# EEZ_DIB_AUX_PS_r3B3.net
KiCad netlist of a schematic drawn in EAGLE
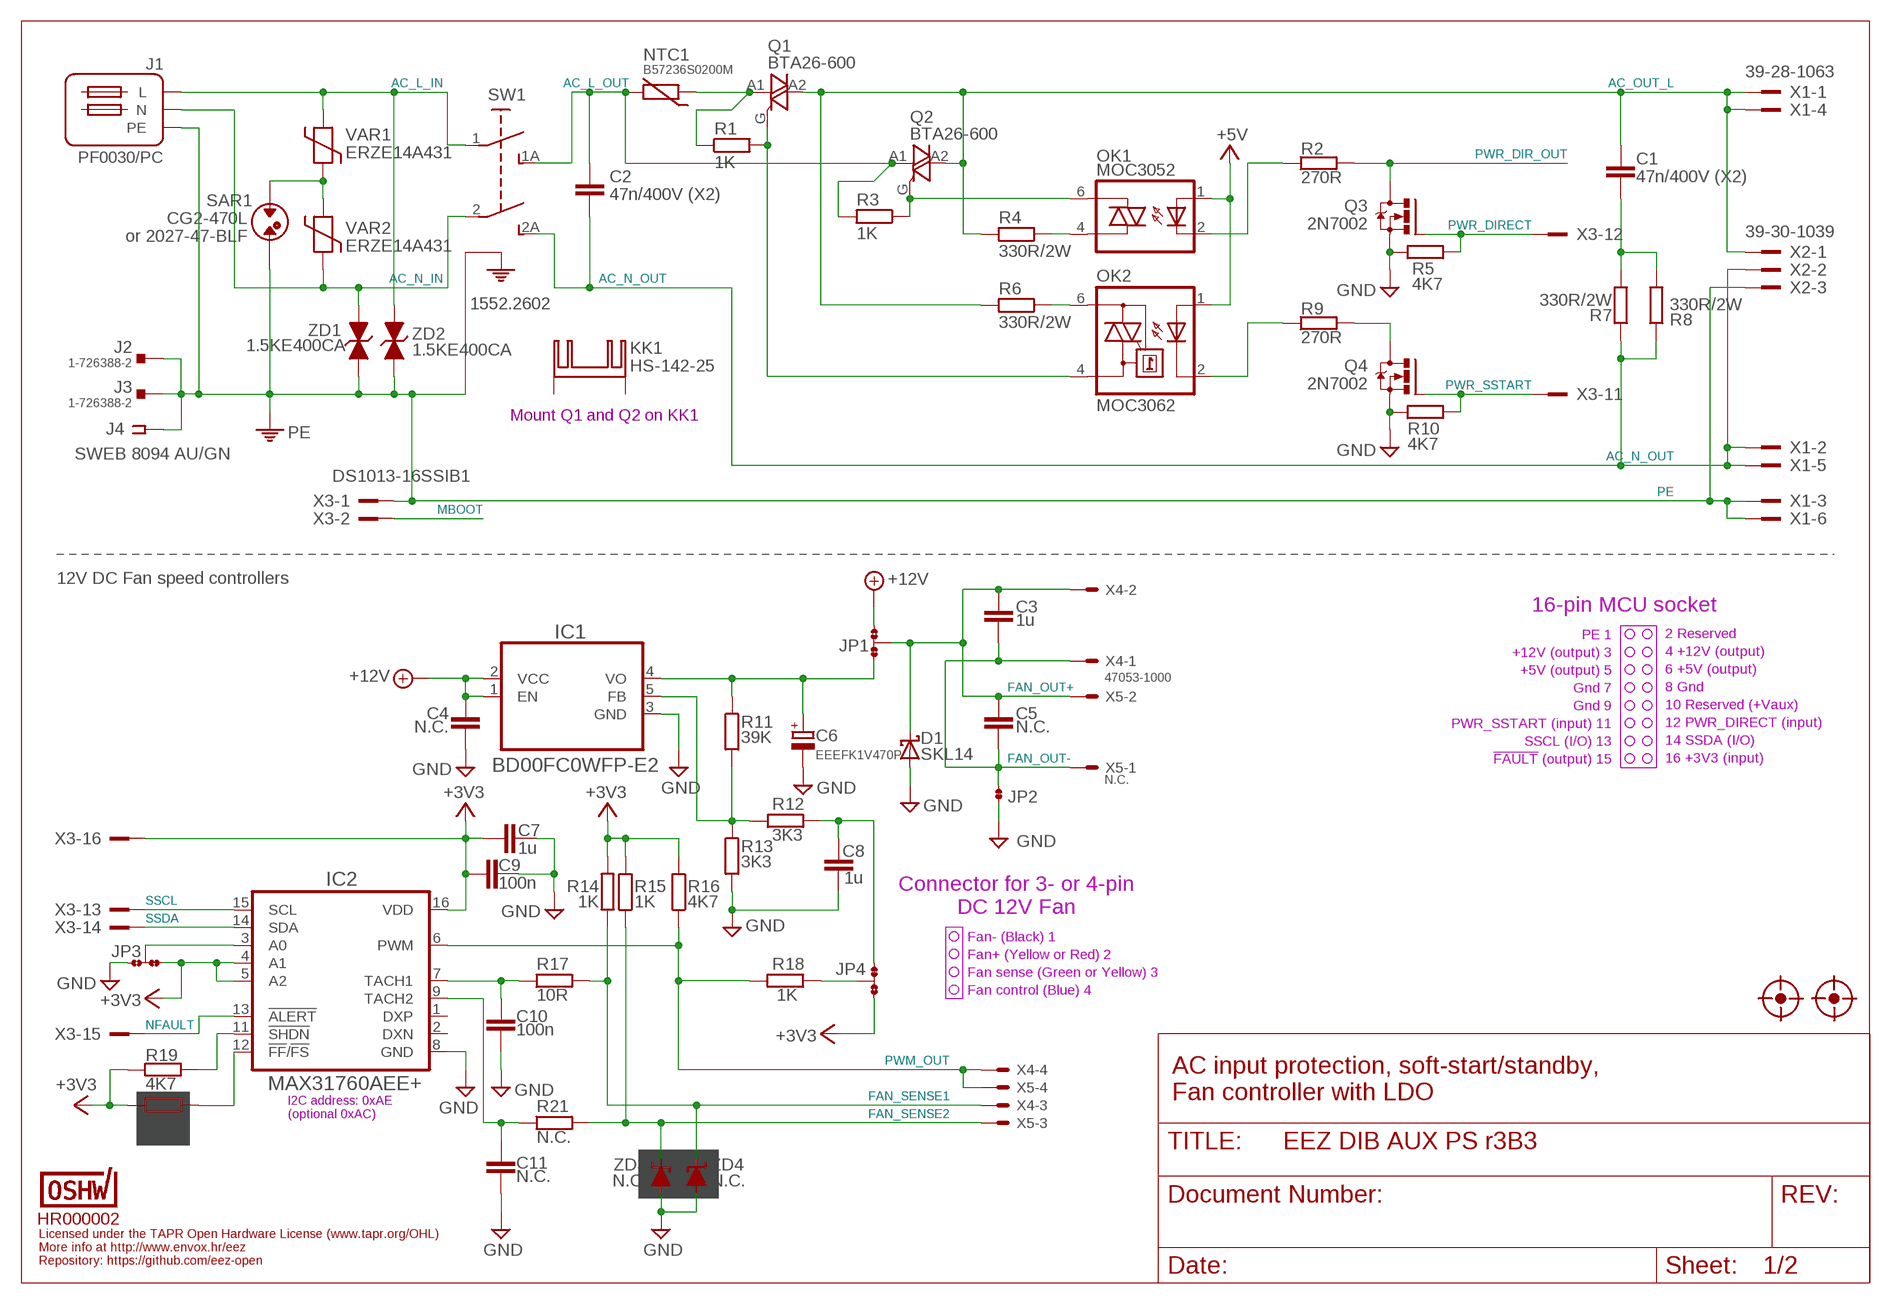
[diagram p0: schematic, sheet 1]
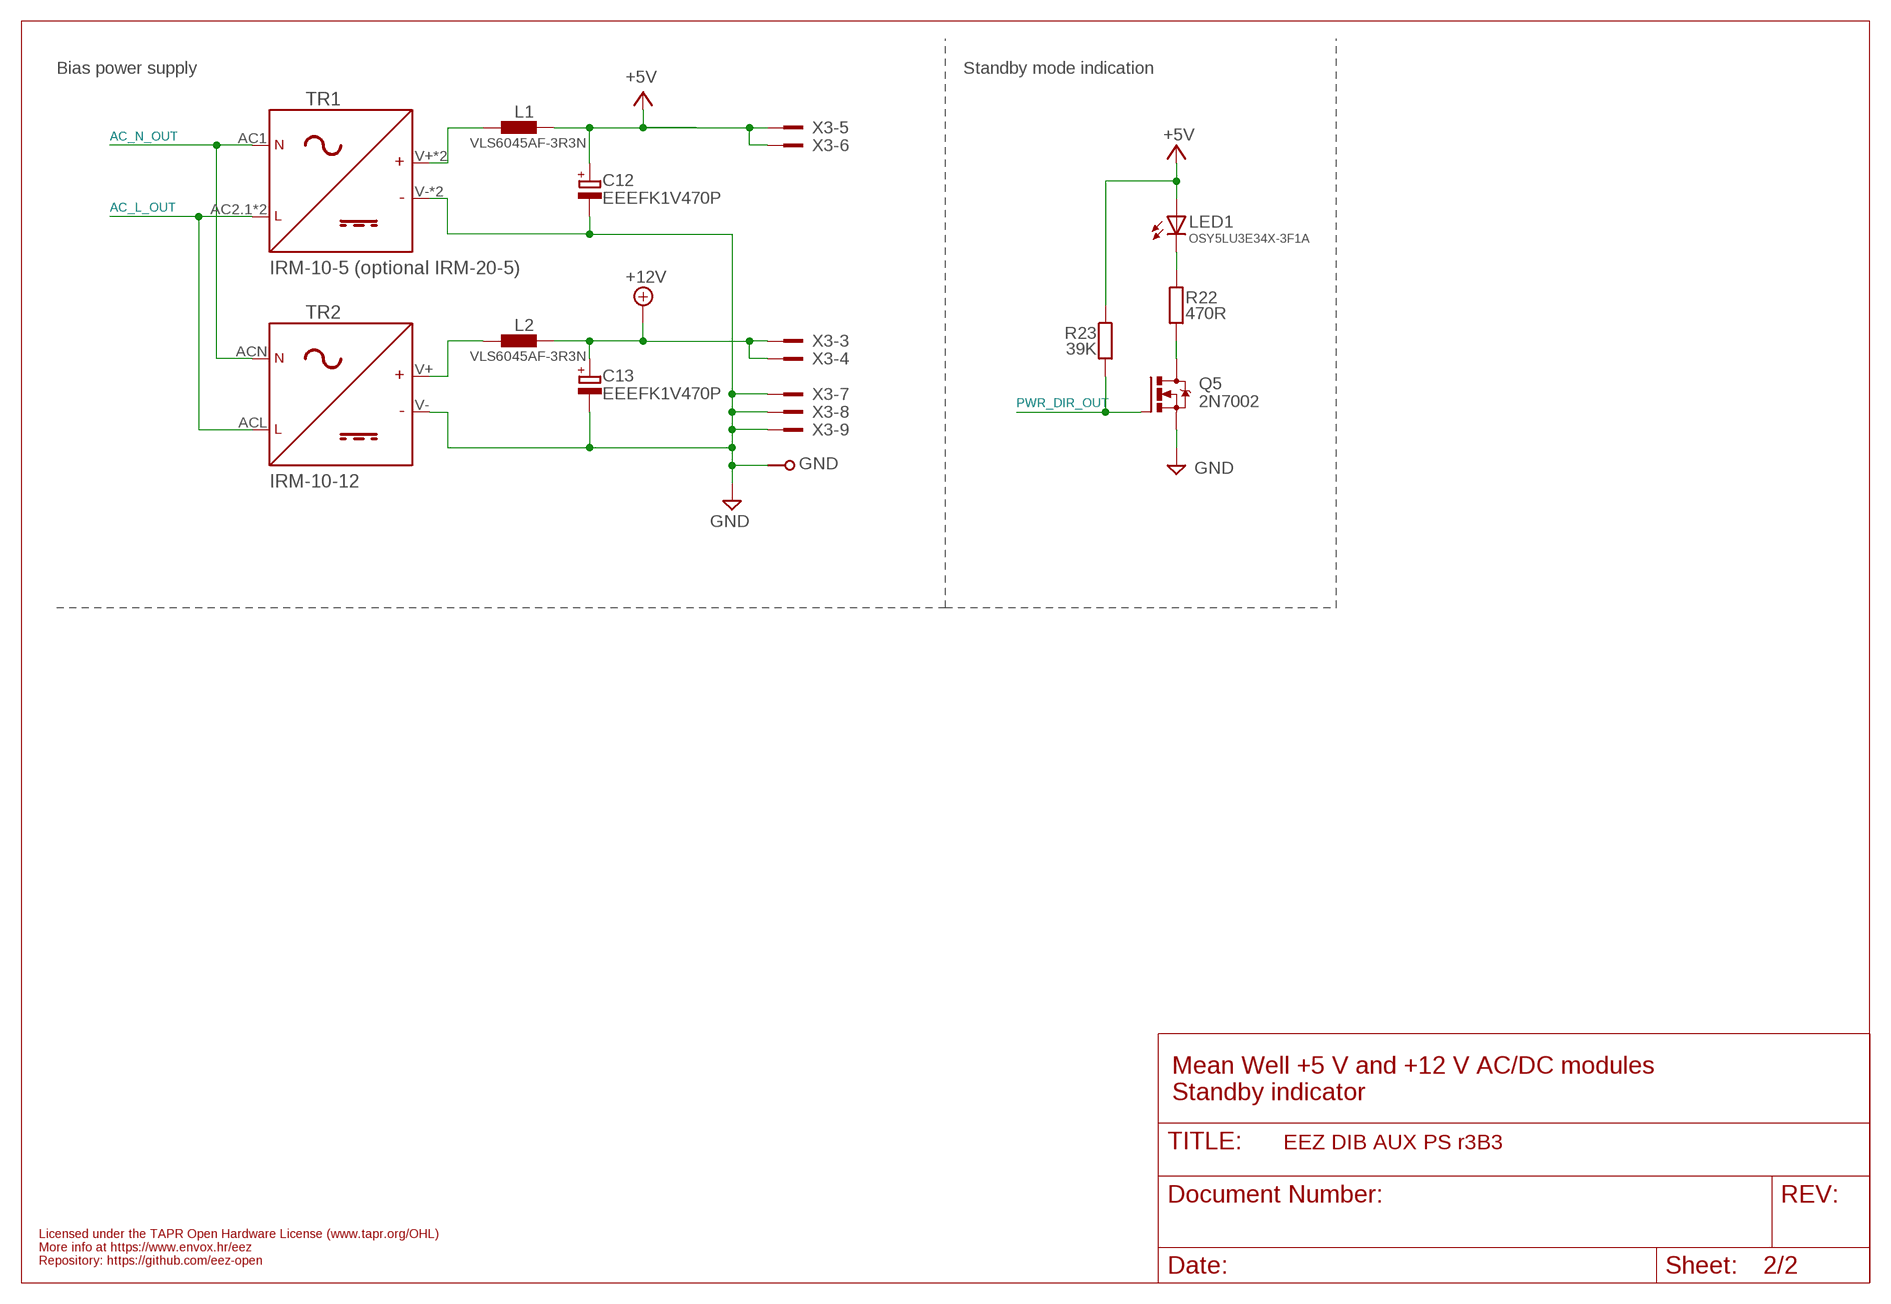
[diagram p1: schematic, sheet 2]

(export (version "E")
  (design (tool "Eeschema 10.0.6"))
  (components
    (comp (ref "C12")
      (value "EEEFK1V470P")
      (footprint "eagle-import:CAPAE660X610N")
      (libsource (lib "eagle-import") (part "ECAPPANASONIC_H"))
    )
    (comp (ref "C13")
      (value "EEEFK1V470P")
      (footprint "eagle-import:CAPAE660X610N")
      (libsource (lib "eagle-import") (part "ECAPPANASONIC_H"))
    )
    (comp (ref "GND")
      (value "PCB_TEST_TABSHIELD")
      (footprint "eagle-import:PCB_SHIELD_TAB")
      (libsource (lib "eagle-import") (part "PCB_TEST_TABSHIELD"))
    )
    (comp (ref "L1")
      (value "VLS6045AF-3R3N")
      (footprint "eagle-import:COILCRAFT_HPI0630")
      (libsource (lib "eagle-import") (part "COILCRAFT_HPI0630"))
    )
    (comp (ref "L2")
      (value "VLS6045AF-3R3N")
      (footprint "eagle-import:COILCRAFT_HPI0630")
      (libsource (lib "eagle-import") (part "COILCRAFT_HPI0630"))
    )
    (comp (ref "LED1")
      (value "OSY5LU3E34X-3F1A")
      (footprint "eagle-import:OSG8")
      (libsource (lib "eagle-import") (part "LEDOSG8"))
    )
    (comp (ref "Q5")
      (value "2N7002")
      (footprint "eagle-import:SOT103P240X110-3N")
      (fields
        (field (name "MPN") "2N7002-7-F")
        (field (name "MPN_1") "2N7002-7-F")
        (field (name "OC_FARNELL") "1713823")
        (field (name "OC_NEWARK") "25R5679")
        (field (name "PACKAGE") "SOT-23-3")
        (field (name "SUPPLIER") "DIODES INC.")
      )
      (libsource (lib "eagle-import") (part "2N7002"))
    )
    (comp (ref "R22")
      (value "470R")
      (footprint "eagle-import:R0805")
      (libsource (lib "eagle-import") (part "R-EU_R0805"))
    )
    (comp (ref "R23")
      (value "39K")
      (footprint "eagle-import:R0805")
      (libsource (lib "eagle-import") (part "R-EU_R0805"))
    )
    (comp (ref "TR1")
      (value "IRM-10-5 (optional IRM-20-5)")
      (footprint "eagle-import:IRM-10_20_COMBO")
      (libsource (lib "eagle-import") (part "AC_DC_ADAPTERIRM10/20"))
    )
    (comp (ref "TR2")
      (value "IRM-10-12")
      (footprint "eagle-import:IRM-10")
      (libsource (lib "eagle-import") (part "AC_DC_ADAPTERIRM10"))
    )
    (comp (ref "X3")
      (value "DS1013-16SSIB1")
      (footprint "eagle-import:IDC-16PIN")
      (libsource (lib "eagle-import") (part "IDC-16PIN"))
    )
    (comp (ref "C1")
      (value "47n/400V (X2)")
      (footprint "eagle-import:C102-054X133")
      (libsource (lib "eagle-import") (part "C-EU102-054X133"))
    )
    (comp (ref "C2")
      (value "47n/400V (X2)")
      (footprint "eagle-import:C102-054X133")
      (libsource (lib "eagle-import") (part "C-EU102-054X133"))
    )
    (comp (ref "C3")
      (value "1u")
      (footprint "eagle-import:C0805")
      (libsource (lib "eagle-import") (part "C-EUC0805"))
    )
    (comp (ref "C4")
      (value "N.C.")
      (footprint "eagle-import:C0805")
      (libsource (lib "eagle-import") (part "C-EUC0805"))
    )
    (comp (ref "C5")
      (value "N.C.")
      (footprint "eagle-import:C0805")
      (libsource (lib "eagle-import") (part "C-EUC0805"))
    )
    (comp (ref "C6")
      (value "EEEFK1V470P")
      (footprint "eagle-import:CAPAE660X610N")
      (libsource (lib "eagle-import") (part "ECAPPANASONIC_H"))
    )
    (comp (ref "C7")
      (value "1u")
      (footprint "eagle-import:C0805")
      (libsource (lib "eagle-import") (part "C-EUC0805"))
    )
    (comp (ref "C8")
      (value "1u")
      (footprint "eagle-import:C0805")
      (libsource (lib "eagle-import") (part "C-EUC0805"))
    )
    (comp (ref "C9")
      (value "100n")
      (footprint "eagle-import:C0603")
      (libsource (lib "eagle-import") (part "C-EUC0603"))
    )
    (comp (ref "C10")
      (value "100n")
      (footprint "eagle-import:C0603")
      (libsource (lib "eagle-import") (part "C-EUC0603"))
    )
    (comp (ref "C11")
      (value "N.C.")
      (footprint "eagle-import:C0603")
      (libsource (lib "eagle-import") (part "C-EUC0603"))
    )
    (comp (ref "D1")
      (value "SKL14")
      (footprint "eagle-import:SOD123")
      (libsource (lib "eagle-import") (part "SCHOTTKYSOD123"))
    )
    (comp (ref "FM1")
      (value "FIDUCIAL")
      (footprint "eagle-import:FIDUCIAL")
      (libsource (lib "eagle-import") (part "FIDUCIAL"))
    )
    (comp (ref "FM2")
      (value "FIDUCIAL")
      (footprint "eagle-import:FIDUCIAL")
      (libsource (lib "eagle-import") (part "FIDUCIAL"))
    )
    (comp (ref "IC1")
      (value "BD00FC0WFP-E2")
      (footprint "eagle-import:TO-252-5")
      (libsource (lib "eagle-import") (part "BD00FC0W"))
    )
    (comp (ref "IC2")
      (value "MAX31760AEE+")
      (footprint "eagle-import:DBQ16")
      (libsource (lib "eagle-import") (part "MAX31760AEE+"))
    )
    (comp (ref "J1")
      (value "PF0030/PC")
      (footprint "eagle-import:PF0030_PC")
      (libsource (lib "eagle-import") (part "PF0030/PC"))
    )
    (comp (ref "J2")
      (value "1-726388-2")
      (footprint "eagle-import:PCB_TAB-4.8MM")
      (libsource (lib "eagle-import") (part "PCB_TAB4.8MM"))
    )
    (comp (ref "J3")
      (value "1-726388-2")
      (footprint "eagle-import:PCB_TAB-4.8MM")
      (libsource (lib "eagle-import") (part "PCB_TAB4.8MM"))
    )
    (comp (ref "J4")
      (value "SWEB 8094 AU/GN")
      (footprint "eagle-import:S16N-PC")
      (libsource (lib "eagle-import") (part "BINDING_POSTCLIFF"))
    )
    (comp (ref "JP1")
      (value "JP3-CUT")
      (footprint "eagle-import:JP3-CUT")
      (libsource (lib "eagle-import") (part "JP3-CUT"))
    )
    (comp (ref "JP2")
      (value "JP2-NOCUT")
      (footprint "eagle-import:JP2-NOCUT")
      (libsource (lib "eagle-import") (part "JP2-NOCUT"))
    )
    (comp (ref "JP3")
      (value "JP3-CUT")
      (footprint "eagle-import:JP3-CUT")
      (libsource (lib "eagle-import") (part "JP3-CUT"))
    )
    (comp (ref "JP4")
      (value "JP3-CUT")
      (footprint "eagle-import:JP3-CUT")
      (libsource (lib "eagle-import") (part "JP3-CUT"))
    )
    (comp (ref "KK1")
      (value "HS-142-25")
      (footprint "eagle-import:SK129")
      (libsource (lib "eagle-import") (part "SK129-PAD"))
    )
    (comp (ref "NTC1")
      (value "B57236S0200M")
      (footprint "eagle-import:NTC_11.5X6_RM5")
      (libsource (lib "eagle-import") (part "NTC11.5X6"))
    )
    (comp (ref "OK1")
      (value "MOC3052")
      (footprint "eagle-import:DIL6-SMD")
      (libsource (lib "eagle-import") (part "MOC305X"))
    )
    (comp (ref "OK2")
      (value "MOC3062")
      (footprint "eagle-import:DIL6-SMD")
      (fields
        (field (name "MF") "FAIRCHILD SEMICONDUCTOR")
        (field (name "MPN") "MOC3033S-M")
        (field (name "MF_1") "FAIRCHILD SEMICONDUCTOR")
        (field (name "MPN_1") "MOC3033S-M")
        (field (name "OC_FARNELL") "unknown")
        (field (name "OC_NEWARK") "05C2878")
      )
      (libsource (lib "eagle-import") (part "MOC30S33"))
    )
    (comp (ref "OSHWA")
      (value "HR000002")
      (footprint "eagle-import:CERT-SMALL-SILK")
      (libsource (lib "eagle-import") (part "OSHWA-CERT-SMALL"))
    )
    (comp (ref "Q1")
      (value "BTA26-600")
      (footprint "eagle-import:TOP3S-1")
      (libsource (lib "eagle-import") (part "BTA26-V"))
    )
    (comp (ref "Q2")
      (value "BTA26-600")
      (footprint "eagle-import:TOP3S-1")
      (libsource (lib "eagle-import") (part "BTA26-V"))
    )
    (comp (ref "Q3")
      (value "2N7002")
      (footprint "eagle-import:SOT103P240X110-3N")
      (fields (field (name "MPN") "2N7002-7-F"))
      (libsource (lib "eagle-import") (part "2N7002"))
    )
    (comp (ref "Q4")
      (value "2N7002")
      (footprint "eagle-import:SOT103P240X110-3N")
      (fields (field (name "MPN") "2N7002-7-F"))
      (libsource (lib "eagle-import") (part "2N7002"))
    )
    (comp (ref "R1")
      (value "1K")
      (footprint "eagle-import:R0805")
      (libsource (lib "eagle-import") (part "R-EU_R0805"))
    )
    (comp (ref "R2")
      (value "270R")
      (footprint "eagle-import:R0805")
      (libsource (lib "eagle-import") (part "R-EU_R0805"))
    )
    (comp (ref "R3")
      (value "1K")
      (footprint "eagle-import:R0805")
      (libsource (lib "eagle-import") (part "R-EU_R0805"))
    )
    (comp (ref "R4")
      (value "330R/2W")
      (footprint "eagle-import:R2512")
      (libsource (lib "eagle-import") (part "R-EU_R2512"))
    )
    (comp (ref "R5")
      (value "4K7")
      (footprint "eagle-import:R0805")
      (libsource (lib "eagle-import") (part "R-EU_R0805"))
    )
    (comp (ref "R6")
      (value "330R/2W")
      (footprint "eagle-import:R2512")
      (libsource (lib "eagle-import") (part "R-EU_R2512"))
    )
    (comp (ref "R7")
      (value "330R/2W")
      (footprint "eagle-import:R2512")
      (libsource (lib "eagle-import") (part "R-EU_R2512"))
    )
    (comp (ref "R8")
      (value "330R/2W")
      (footprint "eagle-import:R2512")
      (libsource (lib "eagle-import") (part "R-EU_R2512"))
    )
    (comp (ref "R9")
      (value "270R")
      (footprint "eagle-import:R0805")
      (libsource (lib "eagle-import") (part "R-EU_R0805"))
    )
    (comp (ref "R10")
      (value "4K7")
      (footprint "eagle-import:R0805")
      (libsource (lib "eagle-import") (part "R-EU_R0805"))
    )
    (comp (ref "R11")
      (value "39K")
      (footprint "eagle-import:R0805")
      (libsource (lib "eagle-import") (part "R-EU_R0805"))
    )
    (comp (ref "R12")
      (value "3K3")
      (footprint "eagle-import:R0805")
      (libsource (lib "eagle-import") (part "R-EU_R0805"))
    )
    (comp (ref "R13")
      (value "3K3")
      (footprint "eagle-import:R0805")
      (libsource (lib "eagle-import") (part "R-EU_R0805"))
    )
    (comp (ref "R14")
      (value "1K")
      (footprint "eagle-import:R0805")
      (libsource (lib "eagle-import") (part "R-EU_R0805"))
    )
    (comp (ref "R15")
      (value "1K")
      (footprint "eagle-import:R0805")
      (libsource (lib "eagle-import") (part "R-EU_R0805"))
    )
    (comp (ref "R16")
      (value "4K7")
      (footprint "eagle-import:R0805")
      (libsource (lib "eagle-import") (part "R-EU_R0805"))
    )
    (comp (ref "R17")
      (value "10R")
      (footprint "eagle-import:R0805")
      (libsource (lib "eagle-import") (part "R-EU_R0805"))
    )
    (comp (ref "R18")
      (value "1K")
      (footprint "eagle-import:R0805")
      (libsource (lib "eagle-import") (part "R-EU_R0805"))
    )
    (comp (ref "R19")
      (value "4K7")
      (footprint "eagle-import:R0805")
      (libsource (lib "eagle-import") (part "R-EU_R0805"))
    )
    (comp (ref "R20")
      (value "N.C.")
      (footprint "eagle-import:R0805")
      (libsource (lib "eagle-import") (part "R-EU_R0805"))
    )
    (comp (ref "R21")
      (value "N.C.")
      (footprint "eagle-import:R0805")
      (libsource (lib "eagle-import") (part "R-EU_R0805"))
    )
    (comp (ref "SAR1")
      (value "CG2-470L")
      (footprint "eagle-import:SAR")
      (libsource (lib "eagle-import") (part "SAR"))
    )
    (comp (ref "SW1")
      (value "1552.2602")
      (footprint "eagle-import:DF62J12S2")
      (libsource (lib "eagle-import") (part "DF62J12S2AHQA"))
    )
    (comp (ref "VAR1")
      (value "ERZE14A431")
      (footprint "eagle-import:VARISTOR_13MM")
      (libsource (lib "eagle-import") (part "VARISTOR-13"))
    )
    (comp (ref "VAR2")
      (value "ERZE14A431")
      (footprint "eagle-import:VARISTOR_13MM")
      (libsource (lib "eagle-import") (part "VARISTOR-13"))
    )
    (comp (ref "X1")
      (value "39-28-1063")
      (footprint "eagle-import:MINIFIT_5566-06A_CRE")
      (libsource (lib "eagle-import") (part "MINIFIT_5566-06A-CRE"))
    )
    (comp (ref "X2")
      (value "39-30-1039")
      (footprint "eagle-import:MINIFIT_39301039_CRE")
      (libsource (lib "eagle-import") (part "MINIFIT_39301039-CREEPAGE"))
    )
    (comp (ref "X4")
      (value "47053-1000")
      (footprint "eagle-import:47053-1000")
      (libsource (lib "eagle-import") (part "47053-1000"))
    )
    (comp (ref "X5")
      (value "N.C.")
      (footprint "eagle-import:47053-1000")
      (libsource (lib "eagle-import") (part "47053-1000"))
    )
    (comp (ref "ZD1")
      (value "1.5KE400CA")
      (footprint "eagle-import:DO201-BIDIR")
      (libsource (lib "eagle-import") (part "1.5KE-BIDIR"))
    )
    (comp (ref "ZD2")
      (value "1.5KE400CA")
      (footprint "eagle-import:DO201-BIDIR")
      (libsource (lib "eagle-import") (part "1.5KE-BIDIR"))
    )
    (comp (ref "ZD3")
      (value "N.C.")
      (footprint "eagle-import:SOD123")
      (libsource (lib "eagle-import") (part "ZENER-DIODESOD123"))
    )
    (comp (ref "ZD4")
      (value "N.C.")
      (footprint "eagle-import:SOD123")
      (libsource (lib "eagle-import") (part "ZENER-DIODESOD123"))
    )
  )
  (nets
    (net (code "1") (name "+3V3") (class "Default")
      (node (ref "C7") (pin "2") (pinfunction "2_2") (pintype "passive"))
      (node (ref "C9") (pin "2") (pinfunction "2_2") (pintype "passive"))
      (node (ref "IC2") (pin "16") (pinfunction "VDD_16") (pintype "power_in"))
      (node (ref "IC2") (pin "4") (pinfunction "A1_4") (pintype "input"))
      (node (ref "IC2") (pin "5") (pinfunction "A2_5") (pintype "input"))
      (node (ref "JP3") (pin "NC") (pinfunction "NC_NC") (pintype "passive"))
      (node (ref "JP4") (pin "NO") (pinfunction "NO_NO") (pintype "passive"))
      (node (ref "R14") (pin "2") (pinfunction "2_2") (pintype "passive"))
      (node (ref "R15") (pin "2") (pinfunction "2_2") (pintype "passive"))
      (node (ref "R16") (pin "2") (pinfunction "2_2") (pintype "passive"))
      (node (ref "R19") (pin "2") (pinfunction "2_2") (pintype "passive"))
      (node (ref "R20") (pin "2") (pinfunction "2_2") (pintype "passive"))
      (node (ref "X3") (pin "16") (pinfunction "1_16") (pintype "passive"))
    )
    (net (code "2") (name "+5V") (class "Default")
      (node (ref "C12") (pin "1") (pinfunction "+_1") (pintype "passive"))
      (node (ref "L1") (pin "2") (pinfunction "2_2") (pintype "passive"))
      (node (ref "LED1") (pin "A") (pinfunction "A_A") (pintype "passive"))
      (node (ref "OK1") (pin "1") (pinfunction "A_1") (pintype "passive"))
      (node (ref "OK2") (pin "1") (pinfunction "A_1") (pintype "passive"))
      (node (ref "R23") (pin "1") (pinfunction "1_1") (pintype "passive"))
      (node (ref "X3") (pin "5") (pinfunction "1_5") (pintype "passive"))
      (node (ref "X3") (pin "6") (pinfunction "1_6") (pintype "passive"))
    )
    (net (code "3") (name "+12V") (class "Default")
      (node (ref "C13") (pin "1") (pinfunction "+_1") (pintype "passive"))
      (node (ref "C4") (pin "1") (pinfunction "1_1") (pintype "passive"))
      (node (ref "IC1") (pin "1") (pinfunction "EN_1") (pintype "passive"))
      (node (ref "IC1") (pin "2") (pinfunction "VCC_2") (pintype "passive"))
      (node (ref "JP1") (pin "NO") (pinfunction "NO_NO") (pintype "passive"))
      (node (ref "L2") (pin "2") (pinfunction "2_2") (pintype "passive"))
      (node (ref "X3") (pin "3") (pinfunction "1_3") (pintype "passive"))
      (node (ref "X3") (pin "4") (pinfunction "1_4") (pintype "passive"))
    )
    (net (code "4") (name "AC_L_IN") (class "Default")
      (node (ref "J1") (pin "L") (pinfunction "L_L") (pintype "bidirectional"))
      (node (ref "SW1") (pin "1") (pinfunction "P_1") (pintype "passive"))
      (node (ref "VAR1") (pin "2") (pinfunction "P$2_2") (pintype "bidirectional"))
      (node (ref "ZD2") (pin "A") (pinfunction "2_A") (pintype "passive"))
    )
    (net (code "5") (name "AC_L_OUT") (class "Default")
      (node (ref "C2") (pin "1") (pinfunction "1_1") (pintype "passive"))
      (node (ref "NTC1") (pin "1") (pinfunction "P$1_1") (pintype "bidirectional"))
      (node (ref "Q2") (pin "A1") (pinfunction "A1_A1") (pintype "passive"))
      (node (ref "R3") (pin "2") (pinfunction "2_2") (pintype "passive"))
      (node (ref "SW1") (pin "1A") (pinfunction "S_1A") (pintype "passive"))
      (node (ref "TR1") (pin "AC2.1") (pinfunction "AC/L_AC2.1") (pintype "input"))
      (node (ref "TR1") (pin "AC2.2") (pinfunction "AC/L_AC2.2") (pintype "input"))
      (node (ref "TR2") (pin "ACL") (pinfunction "AC/L_ACL") (pintype "input"))
    )
    (net (code "6") (name "AC_N_IN") (class "Default")
      (node (ref "J1") (pin "N") (pinfunction "N_N") (pintype "bidirectional"))
      (node (ref "SW1") (pin "2") (pinfunction "P1_2") (pintype "passive"))
      (node (ref "VAR2") (pin "1") (pinfunction "P$1_1") (pintype "bidirectional"))
      (node (ref "ZD1") (pin "A") (pinfunction "2_A") (pintype "passive"))
    )
    (net (code "7") (name "AC_N_OUT") (class "Default")
      (node (ref "C2") (pin "2") (pinfunction "2_2") (pintype "passive"))
      (node (ref "R7") (pin "1") (pinfunction "1_1") (pintype "passive"))
      (node (ref "R8") (pin "1") (pinfunction "1_1") (pintype "passive"))
      (node (ref "SW1") (pin "2A") (pinfunction "S1_2A") (pintype "passive"))
      (node (ref "TR1") (pin "AC1") (pinfunction "AC/N_AC1") (pintype "input"))
      (node (ref "TR2") (pin "ACN") (pinfunction "AC/N_ACN") (pintype "input"))
      (node (ref "X1") (pin "2") (pinfunction "1_2") (pintype "passive"))
      (node (ref "X1") (pin "5") (pinfunction "1_5") (pintype "passive"))
      (node (ref "X2") (pin "2") (pinfunction "1_2") (pintype "passive"))
    )
    (net (code "8") (name "AC_OUT_L") (class "Default")
      (node (ref "C1") (pin "1") (pinfunction "1_1") (pintype "passive"))
      (node (ref "Q1") (pin "A2") (pinfunction "A2_A2") (pintype "passive"))
      (node (ref "Q2") (pin "A2") (pinfunction "A2_A2") (pintype "passive"))
      (node (ref "R4") (pin "2") (pinfunction "2_2") (pintype "passive"))
      (node (ref "R6") (pin "2") (pinfunction "2_2") (pintype "passive"))
      (node (ref "X1") (pin "1") (pinfunction "1_1") (pintype "passive"))
      (node (ref "X1") (pin "4") (pinfunction "1_4") (pintype "passive"))
      (node (ref "X2") (pin "1") (pinfunction "1_1") (pintype "passive"))
    )
    (net (code "9") (name "FAN_OUT+") (class "Default")
      (node (ref "C3") (pin "1") (pinfunction "1_1") (pintype "passive"))
      (node (ref "C5") (pin "1") (pinfunction "1_1") (pintype "passive"))
      (node (ref "D1") (pin "C") (pinfunction "C_C") (pintype "passive"))
      (node (ref "JP1") (pin "COM") (pinfunction "COM_COM") (pintype "passive"))
      (node (ref "X4") (pin "2") (pinfunction "S_2") (pintype "passive"))
      (node (ref "X5") (pin "2") (pinfunction "S_2") (pintype "passive"))
    )
    (net (code "10") (name "FAN_OUT-") (class "Default")
      (node (ref "C3") (pin "2") (pinfunction "2_2") (pintype "passive"))
      (node (ref "C5") (pin "2") (pinfunction "2_2") (pintype "passive"))
      (node (ref "JP2") (pin "2") (pinfunction "2_2") (pintype "passive"))
      (node (ref "X4") (pin "1") (pinfunction "S_1") (pintype "passive"))
      (node (ref "X5") (pin "1") (pinfunction "S_1") (pintype "passive"))
    )
    (net (code "11") (name "FAN_SENSE1") (class "Default")
      (node (ref "R14") (pin "1") (pinfunction "1_1") (pintype "passive"))
      (node (ref "R17") (pin "2") (pinfunction "2_2") (pintype "passive"))
      (node (ref "X4") (pin "3") (pinfunction "S_3") (pintype "passive"))
      (node (ref "ZD4") (pin "C") (pinfunction "C_C") (pintype "passive"))
    )
    (net (code "12") (name "FAN_SENSE2") (class "Default")
      (node (ref "R15") (pin "1") (pinfunction "1_1") (pintype "passive"))
      (node (ref "R21") (pin "2") (pinfunction "2_2") (pintype "passive"))
      (node (ref "X5") (pin "3") (pinfunction "S_3") (pintype "passive"))
      (node (ref "ZD3") (pin "C") (pinfunction "C_C") (pintype "passive"))
    )
    (net (code "13") (name "GND") (class "Default")
      (node (ref "C10") (pin "2") (pinfunction "2_2") (pintype "passive"))
      (node (ref "C11") (pin "2") (pinfunction "2_2") (pintype "passive"))
      (node (ref "C12") (pin "2") (pinfunction "-_2") (pintype "passive"))
      (node (ref "C13") (pin "2") (pinfunction "-_2") (pintype "passive"))
      (node (ref "C4") (pin "2") (pinfunction "2_2") (pintype "passive"))
      (node (ref "C6") (pin "2") (pinfunction "-_2") (pintype "passive"))
      (node (ref "C7") (pin "1") (pinfunction "1_1") (pintype "passive"))
      (node (ref "C8") (pin "2") (pinfunction "2_2") (pintype "passive"))
      (node (ref "C9") (pin "1") (pinfunction "1_1") (pintype "passive"))
      (node (ref "D1") (pin "A") (pinfunction "A_A") (pintype "passive"))
      (node (ref "GND") (pin "1") (pinfunction "P$1_1") (pintype "bidirectional"))
      (node (ref "IC1") (pin "3") (pinfunction "GND_3") (pintype "passive"))
      (node (ref "IC2") (pin "8") (pinfunction "GND_8") (pintype "power_in"))
      (node (ref "JP2") (pin "1") (pinfunction "1_1") (pintype "passive"))
      (node (ref "JP3") (pin "NO") (pinfunction "NO_NO") (pintype "passive"))
      (node (ref "Q3") (pin "2") (pinfunction "S_2") (pintype "passive"))
      (node (ref "Q4") (pin "2") (pinfunction "S_2") (pintype "passive"))
      (node (ref "Q5") (pin "2") (pinfunction "S_2") (pintype "passive"))
      (node (ref "R10") (pin "1") (pinfunction "1_1") (pintype "passive"))
      (node (ref "R13") (pin "2") (pinfunction "2_2") (pintype "passive"))
      (node (ref "R5") (pin "1") (pinfunction "1_1") (pintype "passive"))
      (node (ref "TR1") (pin "V-") (pinfunction "-_V-") (pintype "passive"))
      (node (ref "TR1") (pin "V-1") (pinfunction "-_V-1") (pintype "passive"))
      (node (ref "TR2") (pin "V-") (pinfunction "-_V-") (pintype "passive"))
      (node (ref "X3") (pin "7") (pinfunction "1_7") (pintype "passive"))
      (node (ref "X3") (pin "8") (pinfunction "1_8") (pintype "passive"))
      (node (ref "X3") (pin "9") (pinfunction "1_9") (pintype "passive"))
      (node (ref "ZD3") (pin "A") (pinfunction "A_A") (pintype "passive"))
      (node (ref "ZD4") (pin "A") (pinfunction "A_A") (pintype "passive"))
    )
    (net (code "14") (name "MBOOT") (class "Default")
      (node (ref "X3") (pin "2") (pinfunction "1_2") (pintype "passive"))
    )
    (net (code "15") (name "NFAULT") (class "Default")
      (node (ref "IC2") (pin "13") (pinfunction "~{ALERT}_13") (pintype "output"))
      (node (ref "X3") (pin "15") (pinfunction "1_15") (pintype "passive"))
    )
    (net (code "16") (name "Net-(C1-Pad2)") (class "Default")
      (node (ref "C1") (pin "2") (pinfunction "2_2") (pintype "passive"))
      (node (ref "R7") (pin "2") (pinfunction "2_2") (pintype "passive"))
      (node (ref "R8") (pin "2") (pinfunction "2_2") (pintype "passive"))
    )
    (net (code "17") (name "Net-(C6-+)") (class "Default")
      (node (ref "C6") (pin "1") (pinfunction "+_1") (pintype "passive"))
      (node (ref "IC1") (pin "4") (pinfunction "VO_4") (pintype "output"))
      (node (ref "JP1") (pin "NC") (pinfunction "NC_NC") (pintype "passive"))
      (node (ref "R11") (pin "1") (pinfunction "1_1") (pintype "passive"))
    )
    (net (code "18") (name "Net-(C8-Pad1)") (class "Default")
      (node (ref "C8") (pin "1") (pinfunction "1_1") (pintype "passive"))
      (node (ref "JP4") (pin "NC") (pinfunction "NC_NC") (pintype "passive"))
      (node (ref "R12") (pin "2") (pinfunction "2_2") (pintype "passive"))
    )
    (net (code "19") (name "Net-(IC1-FB)") (class "Default")
      (node (ref "IC1") (pin "5") (pinfunction "FB_5") (pintype "passive"))
      (node (ref "R11") (pin "2") (pinfunction "2_2") (pintype "passive"))
      (node (ref "R12") (pin "1") (pinfunction "1_1") (pintype "passive"))
      (node (ref "R13") (pin "1") (pinfunction "1_1") (pintype "passive"))
    )
    (net (code "20") (name "Net-(IC2-A0)") (class "Default")
      (node (ref "IC2") (pin "3") (pinfunction "A0_3") (pintype "input"))
      (node (ref "JP3") (pin "COM") (pinfunction "COM_COM") (pintype "passive"))
    )
    (net (code "21") (name "Net-(IC2-TACH1)") (class "Default")
      (node (ref "C10") (pin "1") (pinfunction "1_1") (pintype "passive"))
      (node (ref "IC2") (pin "7") (pinfunction "TACH1_7") (pintype "input"))
      (node (ref "R17") (pin "1") (pinfunction "1_1") (pintype "passive"))
    )
    (net (code "22") (name "Net-(IC2-TACH2)") (class "Default")
      (node (ref "C11") (pin "1") (pinfunction "1_1") (pintype "passive"))
      (node (ref "IC2") (pin "9") (pinfunction "TACH2_9") (pintype "input"))
      (node (ref "R21") (pin "1") (pinfunction "1_1") (pintype "passive"))
    )
    (net (code "23") (name "Net-(IC2-~{FF}{slash}~{FS})") (class "Default")
      (node (ref "IC2") (pin "12") (pinfunction "~{FF}/~{FS}_12") (pintype "bidirectional"))
      (node (ref "R20") (pin "1") (pinfunction "1_1") (pintype "passive"))
    )
    (net (code "24") (name "Net-(IC2-~{SHDN})") (class "Default")
      (node (ref "IC2") (pin "11") (pinfunction "~{SHDN}_11") (pintype "output"))
      (node (ref "R19") (pin "1") (pinfunction "1_1") (pintype "passive"))
    )
    (net (code "25") (name "Net-(JP4-PadCOM)") (class "Default")
      (node (ref "JP4") (pin "COM") (pinfunction "COM_COM") (pintype "passive"))
      (node (ref "R18") (pin "1") (pinfunction "1_1") (pintype "passive"))
    )
    (net (code "26") (name "Net-(L1-Pad1)") (class "Default")
      (node (ref "L1") (pin "1") (pinfunction "1_1") (pintype "passive"))
      (node (ref "TR1") (pin "V+") (pinfunction "+_V+") (pintype "passive"))
      (node (ref "TR1") (pin "V+1") (pinfunction "+_V+1") (pintype "passive"))
    )
    (net (code "27") (name "Net-(LED1-PadC)") (class "Default")
      (node (ref "LED1") (pin "C") (pinfunction "C_C") (pintype "passive"))
      (node (ref "R22") (pin "1") (pinfunction "1_1") (pintype "passive"))
    )
    (net (code "28") (name "Net-(NTC1-P$2)") (class "Default")
      (node (ref "NTC1") (pin "2") (pinfunction "P$2_2") (pintype "bidirectional"))
      (node (ref "Q1") (pin "A1") (pinfunction "A1_A1") (pintype "passive"))
      (node (ref "R1") (pin "1") (pinfunction "1_1") (pintype "passive"))
    )
    (net (code "29") (name "Net-(OK1-A1)") (class "Default")
      (node (ref "OK1") (pin "4") (pinfunction "A1_4") (pintype "passive"))
      (node (ref "R4") (pin "1") (pinfunction "1_1") (pintype "passive"))
    )
    (net (code "30") (name "Net-(OK1-A2)") (class "Default")
      (node (ref "OK1") (pin "6") (pinfunction "A2_6") (pintype "passive"))
      (node (ref "Q2") (pin "G") (pinfunction "G_G") (pintype "passive"))
      (node (ref "R3") (pin "1") (pinfunction "1_1") (pintype "passive"))
    )
    (net (code "31") (name "Net-(OK1-C)") (class "Default")
      (node (ref "OK1") (pin "2") (pinfunction "C_2") (pintype "passive"))
      (node (ref "R2") (pin "1") (pinfunction "1_1") (pintype "passive"))
    )
    (net (code "32") (name "Net-(OK2-A1)") (class "Default")
      (node (ref "OK2") (pin "4") (pinfunction "A1_4") (pintype "passive"))
      (node (ref "Q1") (pin "G") (pinfunction "G_G") (pintype "passive"))
      (node (ref "R1") (pin "2") (pinfunction "2_2") (pintype "passive"))
    )
    (net (code "33") (name "Net-(OK2-A2)") (class "Default")
      (node (ref "OK2") (pin "6") (pinfunction "A2_6") (pintype "passive"))
      (node (ref "R6") (pin "1") (pinfunction "1_1") (pintype "passive"))
    )
    (net (code "34") (name "Net-(OK2-C)") (class "Default")
      (node (ref "OK2") (pin "2") (pinfunction "C_2") (pintype "passive"))
      (node (ref "R9") (pin "1") (pinfunction "1_1") (pintype "passive"))
    )
    (net (code "35") (name "Net-(Q4-D)") (class "Default")
      (node (ref "Q4") (pin "3") (pinfunction "D_3") (pintype "passive"))
      (node (ref "R9") (pin "2") (pinfunction "2_2") (pintype "passive"))
    )
    (net (code "36") (name "Net-(Q5-D)") (class "Default")
      (node (ref "Q5") (pin "3") (pinfunction "D_3") (pintype "passive"))
      (node (ref "R22") (pin "2") (pinfunction "2_2") (pintype "passive"))
    )
    (net (code "37") (name "Net-(TR2-+)") (class "Default")
      (node (ref "L2") (pin "1") (pinfunction "1_1") (pintype "passive"))
      (node (ref "TR2") (pin "V+") (pinfunction "+_V+") (pintype "passive"))
    )
    (net (code "38") (name "Net-(VAR1-P$1)") (class "Default")
      (node (ref "SAR1") (pin "P$1") (pinfunction "P$1_P$1") (pintype "bidirectional"))
      (node (ref "VAR1") (pin "1") (pinfunction "P$1_1") (pintype "bidirectional"))
      (node (ref "VAR2") (pin "2") (pinfunction "P$2_2") (pintype "bidirectional"))
    )
    (net (code "39") (name "PE") (class "Default")
      (node (ref "J1") (pin "PE") (pinfunction "PE_PE") (pintype "bidirectional"))
      (node (ref "J2") (pin "1") (pinfunction "P$1_1") (pintype "bidirectional"))
      (node (ref "J2") (pin "2") (pinfunction "P$1_2") (pintype "bidirectional"))
      (node (ref "J3") (pin "1") (pinfunction "P$1_1") (pintype "bidirectional"))
      (node (ref "J3") (pin "2") (pinfunction "P$1_2") (pintype "bidirectional"))
      (node (ref "J4") (pin "1") (pinfunction "1_1") (pintype "passive"))
      (node (ref "J4") (pin "NC1") (pinfunction "1_NC1") (pintype "passive"))
      (node (ref "J4") (pin "NC2") (pinfunction "1_NC2") (pintype "passive"))
      (node (ref "J4") (pin "NC3") (pinfunction "1_NC3") (pintype "passive"))
      (node (ref "J4") (pin "NC4") (pinfunction "1_NC4") (pintype "passive"))
      (node (ref "SAR1") (pin "P$2") (pinfunction "P$2_P$2") (pintype "bidirectional"))
      (node (ref "SW1") (pin "PE1") (pinfunction "PE_PE1") (pintype "power_in"))
      (node (ref "SW1") (pin "PE2") (pinfunction "PE_PE2") (pintype "power_in"))
      (node (ref "X1") (pin "3") (pinfunction "1_3") (pintype "passive"))
      (node (ref "X1") (pin "6") (pinfunction "1_6") (pintype "passive"))
      (node (ref "X2") (pin "3") (pinfunction "1_3") (pintype "passive"))
      (node (ref "X3") (pin "1") (pinfunction "1_1") (pintype "passive"))
      (node (ref "ZD1") (pin "C") (pinfunction "1_C") (pintype "passive"))
      (node (ref "ZD2") (pin "C") (pinfunction "1_C") (pintype "passive"))
    )
    (net (code "40") (name "PWM_OUT") (class "Default")
      (node (ref "IC2") (pin "6") (pinfunction "PWM_6") (pintype "output"))
      (node (ref "R16") (pin "1") (pinfunction "1_1") (pintype "passive"))
      (node (ref "R18") (pin "2") (pinfunction "2_2") (pintype "passive"))
      (node (ref "X4") (pin "4") (pinfunction "S_4") (pintype "passive"))
      (node (ref "X5") (pin "4") (pinfunction "S_4") (pintype "passive"))
    )
    (net (code "41") (name "PWR_DIRECT") (class "Default")
      (node (ref "Q3") (pin "1") (pinfunction "G_1") (pintype "passive"))
      (node (ref "R5") (pin "2") (pinfunction "2_2") (pintype "passive"))
      (node (ref "X3") (pin "12") (pinfunction "1_12") (pintype "passive"))
    )
    (net (code "42") (name "PWR_DIR_OUT") (class "Default")
      (node (ref "Q3") (pin "3") (pinfunction "D_3") (pintype "passive"))
      (node (ref "Q5") (pin "1") (pinfunction "G_1") (pintype "passive"))
      (node (ref "R2") (pin "2") (pinfunction "2_2") (pintype "passive"))
      (node (ref "R23") (pin "2") (pinfunction "2_2") (pintype "passive"))
    )
    (net (code "43") (name "PWR_SSTART") (class "Default")
      (node (ref "Q4") (pin "1") (pinfunction "G_1") (pintype "passive"))
      (node (ref "R10") (pin "2") (pinfunction "2_2") (pintype "passive"))
      (node (ref "X3") (pin "11") (pinfunction "1_11") (pintype "passive"))
    )
    (net (code "44") (name "SSCL") (class "Default")
      (node (ref "IC2") (pin "15") (pinfunction "SCL_15") (pintype "input"))
      (node (ref "X3") (pin "13") (pinfunction "1_13") (pintype "passive"))
    )
    (net (code "45") (name "SSDA") (class "Default")
      (node (ref "IC2") (pin "14") (pinfunction "SDA_14") (pintype "bidirectional"))
      (node (ref "X3") (pin "14") (pinfunction "1_14") (pintype "passive"))
    )
    (net (code "46") (name "unconnected-(IC2-DXN-Pad2)") (class "Default")
      (node (ref "IC2") (pin "2") (pinfunction "DXN_2") (pintype "input"))
    )
    (net (code "47") (name "unconnected-(IC2-DXP-Pad1)") (class "Default")
      (node (ref "IC2") (pin "1") (pinfunction "DXP_1") (pintype "input"))
    )
    (net (code "48") (name "unconnected-(KK1-K-PadA2,5)") (class "Default")
      (node (ref "KK1") (pin "A2,5") (pinfunction "K_A2,5") (pintype "passive"))
    )
    (net (code "49") (name "unconnected-(KK1-K-PadB2,5)") (class "Default")
      (node (ref "KK1") (pin "B2,5") (pinfunction "K_B2,5") (pintype "passive"))
    )
  )
)
